# halloween-mask-v2.net
KiCad netlist of a schematic drawn in EAGLE
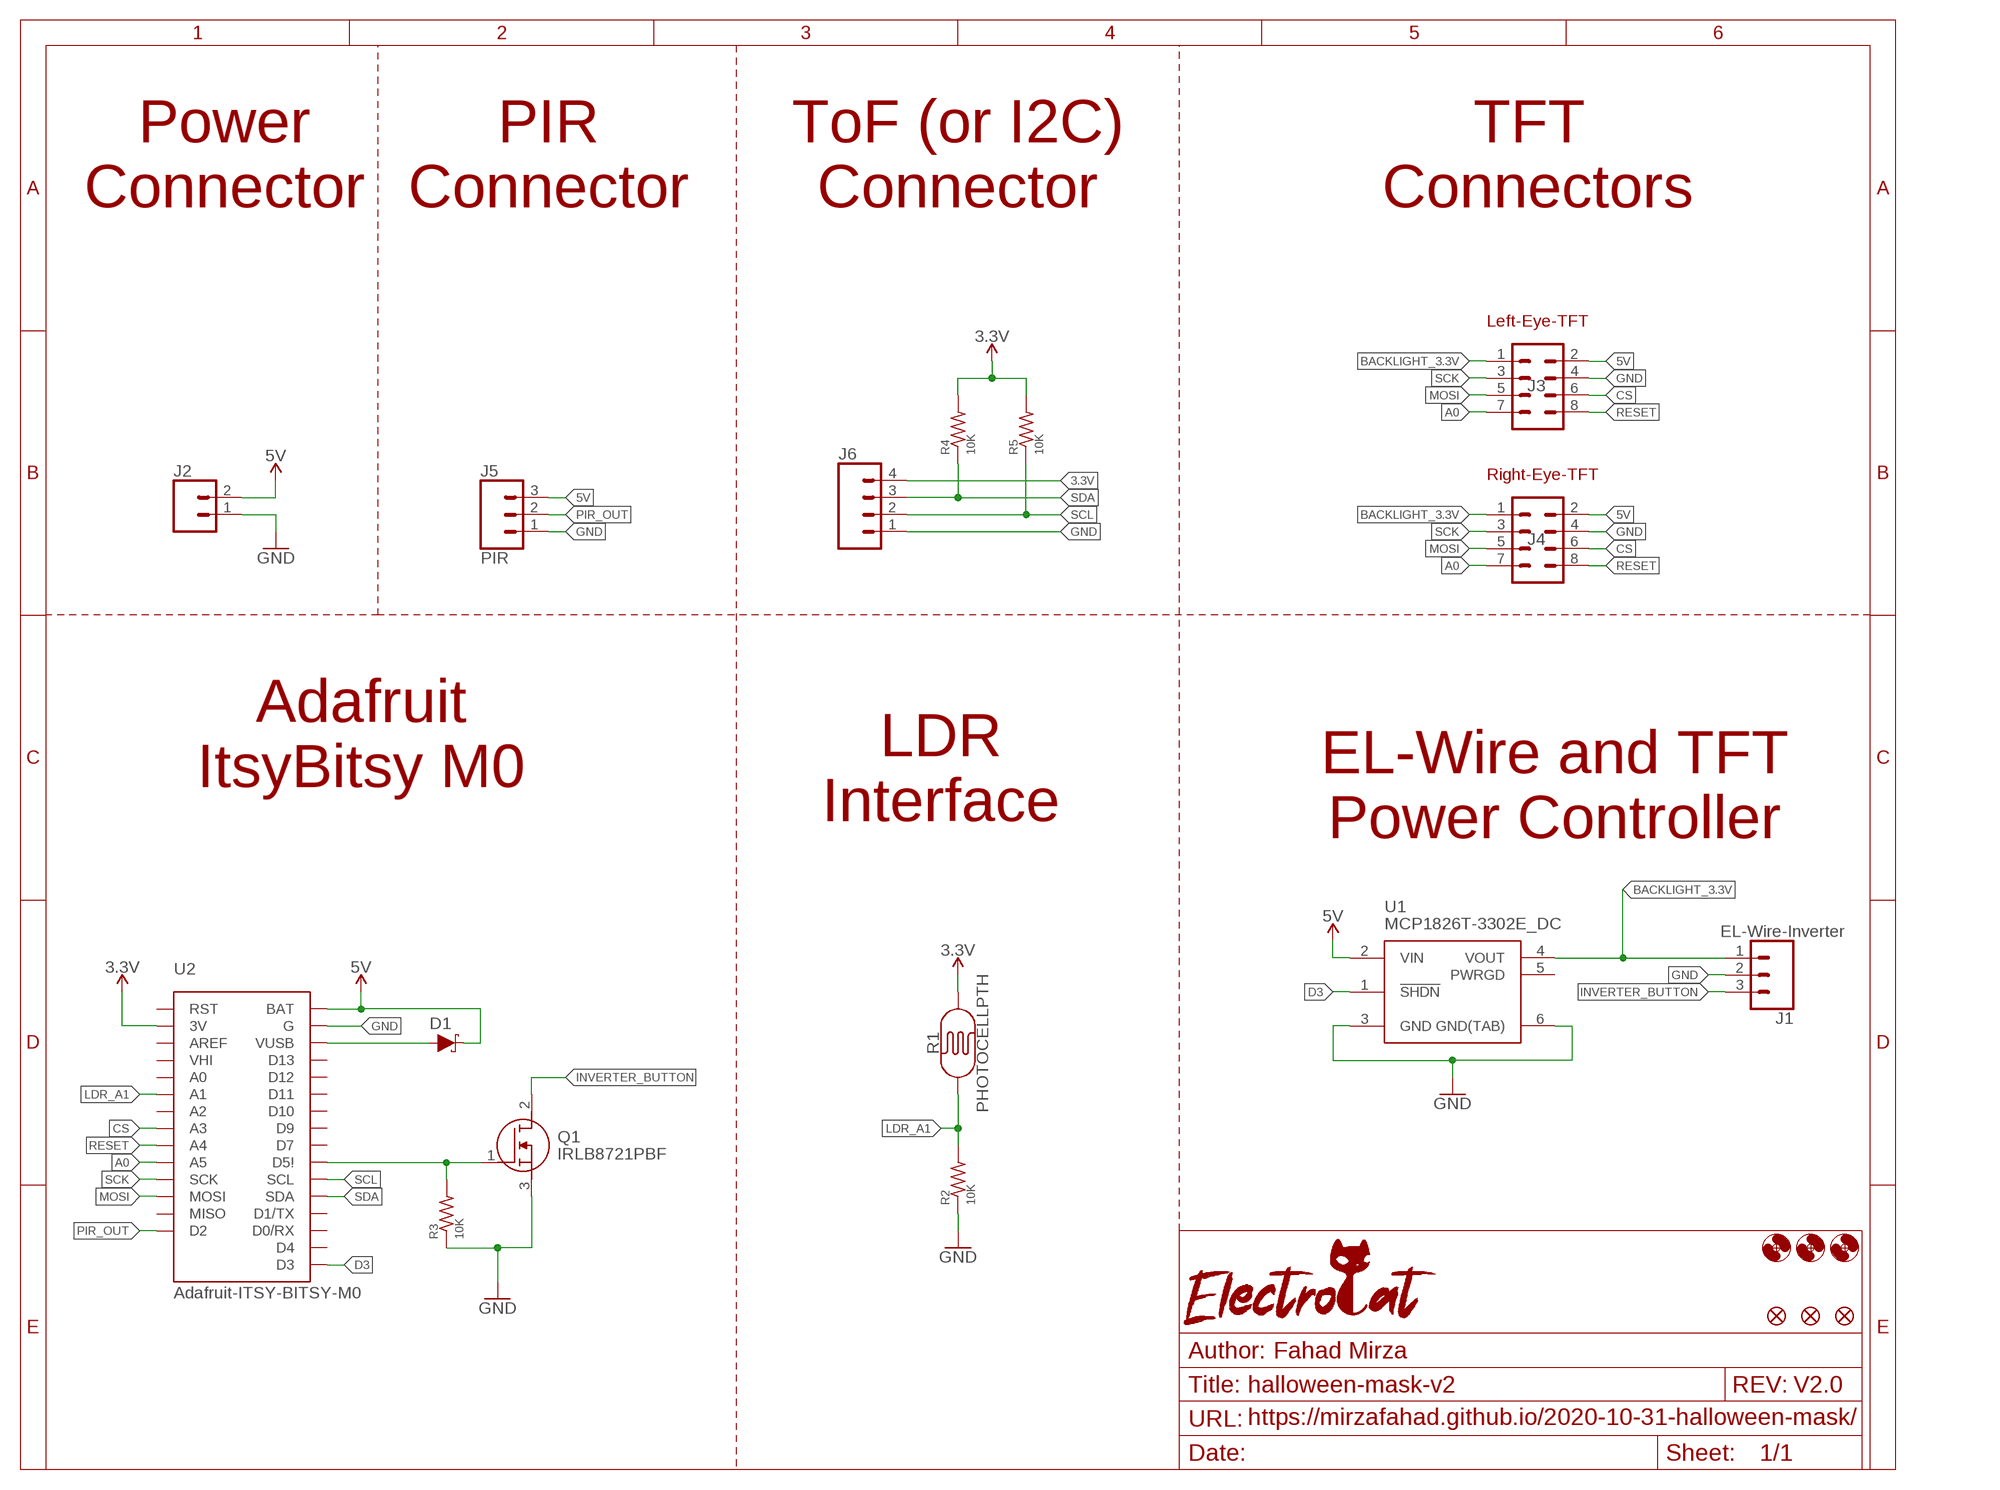
[diagram p0: schematic, sheet 1]

(export (version "E")
  (design (tool "Eeschema 10.0.6"))
  (components
    (comp (ref "D1")
      (value "DIODE-SCHOTTKY-MBR130T1G")
      (footprint "eagle-import:SOD-123")
      (libsource (lib "eagle-import") (part "DIODE-SCHOTTKY-MBR130T1G"))
    )
    (comp (ref "FD1")
      (value "FIDUCIAL0.2MM")
      (footprint "eagle-import:FIDUCIAL-0.2MM")
      (libsource (lib "eagle-import") (part "FIDUCIAL0.2MM"))
    )
    (comp (ref "FD2")
      (value "FIDUCIAL0.2MM")
      (footprint "eagle-import:FIDUCIAL-0.2MM")
      (libsource (lib "eagle-import") (part "FIDUCIAL0.2MM"))
    )
    (comp (ref "FD3")
      (value "FIDUCIAL0.2MM")
      (footprint "eagle-import:FIDUCIAL-0.2MM")
      (libsource (lib "eagle-import") (part "FIDUCIAL0.2MM"))
    )
    (comp (ref "H1")
      (value "MOUNT-HOLE2.8")
      (footprint "eagle-import:2,8")
      (libsource (lib "eagle-import") (part "MOUNT-HOLE2.8"))
    )
    (comp (ref "H2")
      (value "MOUNT-HOLE2.8")
      (footprint "eagle-import:2,8")
      (libsource (lib "eagle-import") (part "MOUNT-HOLE2.8"))
    )
    (comp (ref "H4")
      (value "MOUNT-HOLE2.8")
      (footprint "eagle-import:2,8")
      (libsource (lib "eagle-import") (part "MOUNT-HOLE2.8"))
    )
    (comp (ref "J1")
      (value "EL-Wire-Inverter")
      (footprint "eagle-import:1X03")
      (libsource (lib "eagle-import") (part "CONN_03"))
    )
    (comp (ref "J2")
      (value "CONN_02LOCK")
      (footprint "eagle-import:1X02_LOCK")
      (libsource (lib "eagle-import") (part "CONN_02LOCK"))
    )
    (comp (ref "J3")
      (value "CONN_04X2")
      (footprint "eagle-import:2X4")
      (libsource (lib "eagle-import") (part "CONN_04X2"))
    )
    (comp (ref "J4")
      (value "CONN_04X2")
      (footprint "eagle-import:2X4")
      (libsource (lib "eagle-import") (part "CONN_04X2"))
    )
    (comp (ref "J5")
      (value "PIR")
      (footprint "eagle-import:1X03_LOCK")
      (libsource (lib "eagle-import") (part "CONN_03LOCK"))
    )
    (comp (ref "J6")
      (value "CONN_04PTH")
      (footprint "eagle-import:1X04")
      (libsource (lib "eagle-import") (part "CONN_04PTH"))
    )
    (comp (ref "Q1")
      (value "IRLB8721PBF")
      (footprint "eagle-import:TO254P483X1016X1994-3P")
      (libsource (lib "eagle-import") (part "IRLB8721PBF"))
    )
    (comp (ref "R1")
      (value "PHOTOCELLPTH")
      (footprint "eagle-import:PHOTOCELL")
      (libsource (lib "eagle-import") (part "PHOTOCELLPTH"))
    )
    (comp (ref "R2")
      (value "10K")
      (footprint "eagle-import:R1206")
      (libsource (lib "eagle-import") (part "SMD-RES-1206"))
    )
    (comp (ref "R3")
      (value "10K")
      (footprint "eagle-import:R1206")
      (libsource (lib "eagle-import") (part "SMD-RES-1206"))
    )
    (comp (ref "R4")
      (value "10K")
      (footprint "eagle-import:R1206")
      (libsource (lib "eagle-import") (part "SMD-RES-1206"))
    )
    (comp (ref "R5")
      (value "10K")
      (footprint "eagle-import:R1206")
      (libsource (lib "eagle-import") (part "SMD-RES-1206"))
    )
    (comp (ref "U1")
      (value "MCP1826T-3302E_DC")
      (footprint "eagle-import:SOT127P706X180-6N")
      (fields
        (field (name "ARROW_PART_NUMBER") "MCP1826T-3302E/DC")
        (field (name "MOUSER_PART_NUMBER") "579-MCP1826T-3302EDC")
      )
      (libsource (lib "eagle-import") (part "MCP1826T-3302E_DC"))
    )
    (comp (ref "U2")
      (value "Adafruit-ITSY-BITSY-M0")
      (footprint "eagle-import:ITSY-BITSY-LESS-PINS")
      (libsource (lib "eagle-import") (part "ITSY-BITSY-LESS-PINS"))
    )
  )
  (nets
    (net (code "1") (name "3.3V") (class "Default")
      (node (ref "J6") (pin "4") (pinfunction "4_4") (pintype "passive"))
      (node (ref "R1") (pin "2") (pinfunction "P$2_2") (pintype "bidirectional"))
      (node (ref "R4") (pin "2") (pinfunction "2_2") (pintype "passive"))
      (node (ref "R5") (pin "2") (pinfunction "2_2") (pintype "passive"))
      (node (ref "U2") (pin "P2") (pinfunction "3V_P2") (pintype "bidirectional"))
    )
    (net (code "2") (name "5V") (class "Default")
      (node (ref "D1") (pin "2") (pinfunction "C_2") (pintype "passive"))
      (node (ref "J2") (pin "2") (pinfunction "2_2") (pintype "passive"))
      (node (ref "J3") (pin "2") (pinfunction "2_2") (pintype "passive"))
      (node (ref "J4") (pin "2") (pinfunction "2_2") (pintype "passive"))
      (node (ref "J5") (pin "3") (pinfunction "3_3") (pintype "passive"))
      (node (ref "U1") (pin "2") (pinfunction "VIN_2") (pintype "input"))
      (node (ref "U2") (pin "P28") (pinfunction "BAT_P28") (pintype "bidirectional"))
    )
    (net (code "3") (name "A0") (class "Default")
      (node (ref "J3") (pin "7") (pinfunction "7_7") (pintype "passive"))
      (node (ref "J4") (pin "7") (pinfunction "7_7") (pintype "passive"))
      (node (ref "U2") (pin "P10") (pinfunction "A5_P10") (pintype "bidirectional"))
    )
    (net (code "4") (name "BACKLIGHT_3.3V") (class "Default")
      (node (ref "J1") (pin "1") (pinfunction "1_1") (pintype "passive"))
      (node (ref "J3") (pin "1") (pinfunction "1_1") (pintype "passive"))
      (node (ref "J4") (pin "1") (pinfunction "1_1") (pintype "passive"))
      (node (ref "U1") (pin "4") (pinfunction "VOUT_4") (pintype "output"))
    )
    (net (code "5") (name "CS") (class "Default")
      (node (ref "J3") (pin "6") (pinfunction "6_6") (pintype "passive"))
      (node (ref "J4") (pin "6") (pinfunction "6_6") (pintype "passive"))
      (node (ref "U2") (pin "P8") (pinfunction "A3_P8") (pintype "bidirectional"))
    )
    (net (code "6") (name "D3") (class "Default")
      (node (ref "U1") (pin "1") (pinfunction "~{SHDN}_1") (pintype "bidirectional"))
      (node (ref "U2") (pin "18") (pinfunction "D3_18") (pintype "bidirectional"))
    )
    (net (code "7") (name "GND") (class "Default")
      (node (ref "J1") (pin "2") (pinfunction "2_2") (pintype "passive"))
      (node (ref "J2") (pin "1") (pinfunction "1_1") (pintype "passive"))
      (node (ref "J3") (pin "4") (pinfunction "4_4") (pintype "passive"))
      (node (ref "J4") (pin "4") (pinfunction "4_4") (pintype "passive"))
      (node (ref "J5") (pin "1") (pinfunction "1_1") (pintype "passive"))
      (node (ref "J6") (pin "1") (pinfunction "1_1") (pintype "passive"))
      (node (ref "Q1") (pin "3") (pinfunction "S_3") (pintype "bidirectional"))
      (node (ref "R2") (pin "1") (pinfunction "1_1") (pintype "passive"))
      (node (ref "R3") (pin "1") (pinfunction "1_1") (pintype "passive"))
      (node (ref "U1") (pin "3") (pinfunction "GND_3") (pintype "power_in"))
      (node (ref "U1") (pin "6") (pinfunction "GND(TAB)_6") (pintype "power_in"))
      (node (ref "U2") (pin "P27") (pinfunction "G_P27") (pintype "bidirectional"))
    )
    (net (code "8") (name "INVERTER_BUTTON") (class "Default")
      (node (ref "J1") (pin "3") (pinfunction "3_3") (pintype "passive"))
      (node (ref "Q1") (pin "2") (pinfunction "D_2") (pintype "bidirectional"))
    )
    (net (code "9") (name "LDR_A1") (class "Default")
      (node (ref "R1") (pin "1") (pinfunction "P$1_1") (pintype "bidirectional"))
      (node (ref "R2") (pin "2") (pinfunction "2_2") (pintype "passive"))
      (node (ref "U2") (pin "P6") (pinfunction "A1_P6") (pintype "bidirectional"))
    )
    (net (code "10") (name "MOSI") (class "Default")
      (node (ref "J3") (pin "5") (pinfunction "5_5") (pintype "passive"))
      (node (ref "J4") (pin "5") (pinfunction "5_5") (pintype "passive"))
      (node (ref "U2") (pin "P12") (pinfunction "MOSI_P12") (pintype "bidirectional"))
    )
    (net (code "11") (name "Net-(D1-A)") (class "Default")
      (node (ref "D1") (pin "1") (pinfunction "A_1") (pintype "passive"))
      (node (ref "U2") (pin "P26") (pinfunction "VUSB_P26") (pintype "bidirectional"))
    )
    (net (code "12") (name "Net-(Q1-G)") (class "Default")
      (node (ref "Q1") (pin "1") (pinfunction "G_1") (pintype "bidirectional"))
      (node (ref "R3") (pin "2") (pinfunction "2_2") (pintype "passive"))
      (node (ref "U2") (pin "P19") (pinfunction "D5~{}_P19") (pintype "bidirectional"))
    )
    (net (code "13") (name "PIR_OUT") (class "Default")
      (node (ref "J5") (pin "2") (pinfunction "2_2") (pintype "passive"))
      (node (ref "U2") (pin "P14") (pinfunction "D2_P14") (pintype "bidirectional"))
    )
    (net (code "14") (name "RESET") (class "Default")
      (node (ref "J3") (pin "8") (pinfunction "8_8") (pintype "passive"))
      (node (ref "J4") (pin "8") (pinfunction "8_8") (pintype "passive"))
      (node (ref "U2") (pin "P9") (pinfunction "A4_P9") (pintype "bidirectional"))
    )
    (net (code "15") (name "SCK") (class "Default")
      (node (ref "J3") (pin "3") (pinfunction "3_3") (pintype "passive"))
      (node (ref "J4") (pin "3") (pinfunction "3_3") (pintype "passive"))
      (node (ref "U2") (pin "P11") (pinfunction "SCK_P11") (pintype "bidirectional"))
    )
    (net (code "16") (name "SCL") (class "Default")
      (node (ref "J6") (pin "2") (pinfunction "2_2") (pintype "passive"))
      (node (ref "R5") (pin "1") (pinfunction "1_1") (pintype "passive"))
      (node (ref "U2") (pin "P18") (pinfunction "SCL_P18") (pintype "bidirectional"))
    )
    (net (code "17") (name "SDA") (class "Default")
      (node (ref "J6") (pin "3") (pinfunction "3_3") (pintype "passive"))
      (node (ref "R4") (pin "1") (pinfunction "1_1") (pintype "passive"))
      (node (ref "U2") (pin "P17") (pinfunction "SDA_P17") (pintype "bidirectional"))
    )
    (net (code "18") (name "unconnected-(U1-PWRGD-Pad5)") (class "Default")
      (node (ref "U1") (pin "5") (pinfunction "PWRGD_5") (pintype "bidirectional"))
    )
    (net (code "19") (name "unconnected-(U2-A0-PadP5)") (class "Default")
      (node (ref "U2") (pin "P5") (pinfunction "A0_P5") (pintype "bidirectional"))
    )
    (net (code "20") (name "unconnected-(U2-A2-PadP7)") (class "Default")
      (node (ref "U2") (pin "P7") (pinfunction "A2_P7") (pintype "bidirectional"))
    )
    (net (code "21") (name "unconnected-(U2-AREF-PadP3)") (class "Default")
      (node (ref "U2") (pin "P3") (pinfunction "AREF_P3") (pintype "bidirectional"))
    )
    (net (code "22") (name "unconnected-(U2-D0{slash}RX-PadP15)") (class "Default")
      (node (ref "U2") (pin "P15") (pinfunction "D0/RX_P15") (pintype "bidirectional"))
    )
    (net (code "23") (name "unconnected-(U2-D1{slash}TX-PadP16)") (class "Default")
      (node (ref "U2") (pin "P16") (pinfunction "D1/TX_P16") (pintype "bidirectional"))
    )
    (net (code "24") (name "unconnected-(U2-D4-Pad19)") (class "Default")
      (node (ref "U2") (pin "19") (pinfunction "D4_19") (pintype "bidirectional"))
    )
    (net (code "25") (name "unconnected-(U2-D7-PadP20)") (class "Default")
      (node (ref "U2") (pin "P20") (pinfunction "D7_P20") (pintype "bidirectional"))
    )
    (net (code "26") (name "unconnected-(U2-D9-PadP21)") (class "Default")
      (node (ref "U2") (pin "P21") (pinfunction "D9_P21") (pintype "bidirectional"))
    )
    (net (code "27") (name "unconnected-(U2-D10-PadP22)") (class "Default")
      (node (ref "U2") (pin "P22") (pinfunction "D10_P22") (pintype "bidirectional"))
    )
    (net (code "28") (name "unconnected-(U2-D11-PadP23)") (class "Default")
      (node (ref "U2") (pin "P23") (pinfunction "D11_P23") (pintype "bidirectional"))
    )
    (net (code "29") (name "unconnected-(U2-D12-PadP24)") (class "Default")
      (node (ref "U2") (pin "P24") (pinfunction "D12_P24") (pintype "bidirectional"))
    )
    (net (code "30") (name "unconnected-(U2-D13-PadP25)") (class "Default")
      (node (ref "U2") (pin "P25") (pinfunction "D13_P25") (pintype "bidirectional"))
    )
    (net (code "31") (name "unconnected-(U2-MISO-PadP13)") (class "Default")
      (node (ref "U2") (pin "P13") (pinfunction "MISO_P13") (pintype "bidirectional"))
    )
    (net (code "32") (name "unconnected-(U2-RST-PadP1)") (class "Default")
      (node (ref "U2") (pin "P1") (pinfunction "RST_P1") (pintype "bidirectional"))
    )
    (net (code "33") (name "unconnected-(U2-VHI-PadP4)") (class "Default")
      (node (ref "U2") (pin "P4") (pinfunction "VHI_P4") (pintype "bidirectional"))
    )
  )
)
